# electromiografo.net
KiCad netlist of a schematic drawn in EAGLE
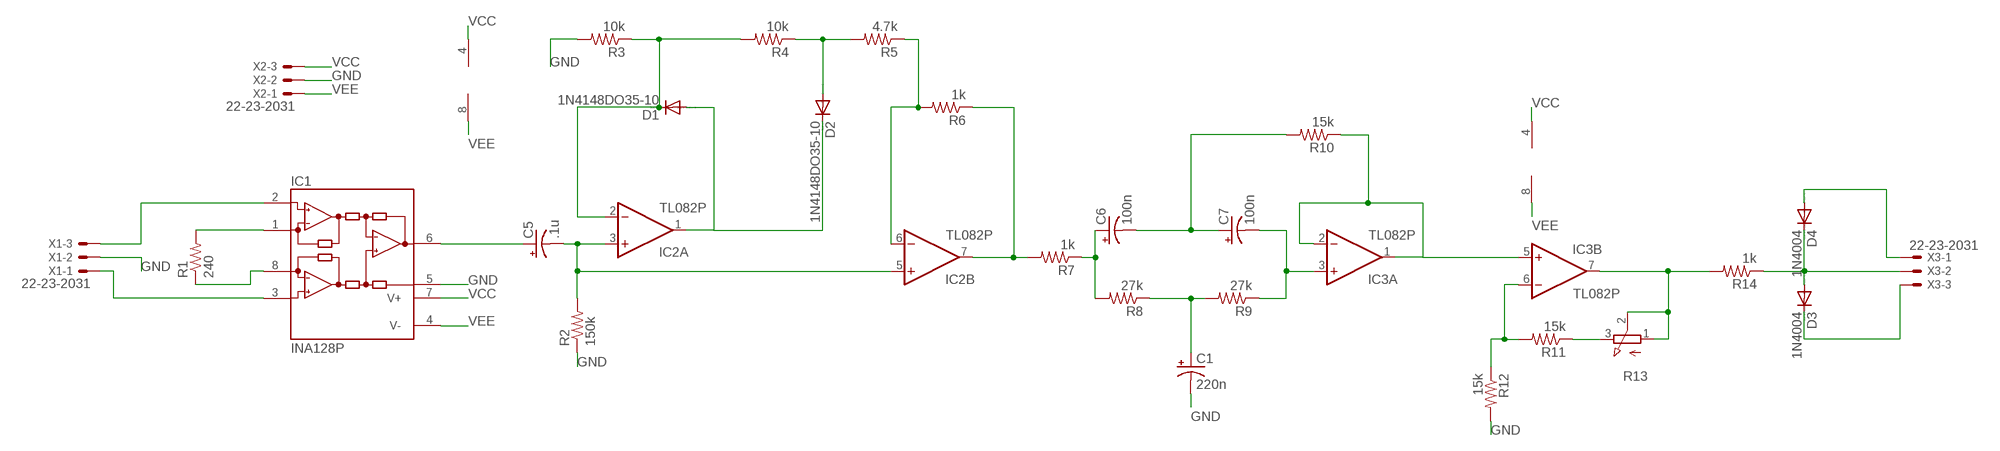
[diagram p0: schematic, sheet 1]

(export (version "E")
  (design (tool "Eeschema 10.0.6"))
  (components
    (comp (ref "C1")
      (value "220n")
      (footprint "eagle-import:E2-5")
      (libsource (lib "eagle-import") (part "CPOL-USE2-5"))
    )
    (comp (ref "C5")
      (value ".1u")
      (footprint "eagle-import:E2-5")
      (libsource (lib "eagle-import") (part "CPOL-USE2-5"))
    )
    (comp (ref "C6")
      (value "100n")
      (footprint "eagle-import:E2-5")
      (libsource (lib "eagle-import") (part "CPOL-USE2-5"))
    )
    (comp (ref "C7")
      (value "100n")
      (footprint "eagle-import:E2-5")
      (libsource (lib "eagle-import") (part "CPOL-USE2-5"))
    )
    (comp (ref "D1")
      (value "1N4148DO35-10")
      (footprint "eagle-import:DO35-10")
      (libsource (lib "eagle-import") (part "1N4148DO35-10"))
    )
    (comp (ref "D2")
      (value "1N4148DO35-10")
      (footprint "eagle-import:DO35-10")
      (libsource (lib "eagle-import") (part "1N4148DO35-10"))
    )
    (comp (ref "D3")
      (value "1N4004")
      (footprint "eagle-import:DO41-10")
      (libsource (lib "eagle-import") (part "1N4004"))
    )
    (comp (ref "D4")
      (value "1N4004")
      (footprint "eagle-import:DO41-10")
      (libsource (lib "eagle-import") (part "1N4004"))
    )
    (comp (ref "IC1")
      (value "INA128P")
      (footprint "eagle-import:DIL08")
      (fields (field (name "MF") "TEXAS INSTRUMENTS"))
      (libsource (lib "eagle-import") (part "INA128P"))
    )
    (comp (ref "IC2")
      (value "TL082P")
      (footprint "eagle-import:DIL08")
      (libsource (lib "eagle-import") (part "TL082P"))
    )
    (comp (ref "IC3")
      (value "TL082P")
      (footprint "eagle-import:DIL08")
      (libsource (lib "eagle-import") (part "TL082P"))
    )
    (comp (ref "R1")
      (value "240")
      (footprint "eagle-import:0207_12")
      (libsource (lib "eagle-import") (part "R-US_0207/12"))
    )
    (comp (ref "R2")
      (value "150k")
      (footprint "eagle-import:0207_12")
      (libsource (lib "eagle-import") (part "R-US_0207/12"))
    )
    (comp (ref "R3")
      (value "10k")
      (footprint "eagle-import:0207_12")
      (libsource (lib "eagle-import") (part "R-US_0207/12"))
    )
    (comp (ref "R4")
      (value "10k")
      (footprint "eagle-import:0207_12")
      (libsource (lib "eagle-import") (part "R-US_0207/12"))
    )
    (comp (ref "R5")
      (value "4.7k")
      (footprint "eagle-import:0207_12")
      (libsource (lib "eagle-import") (part "R-US_0207/12"))
    )
    (comp (ref "R6")
      (value "1k")
      (footprint "eagle-import:0207_12")
      (libsource (lib "eagle-import") (part "R-US_0207/12"))
    )
    (comp (ref "R7")
      (value "1k")
      (footprint "eagle-import:0207_12")
      (libsource (lib "eagle-import") (part "R-US_0207/12"))
    )
    (comp (ref "R8")
      (value "27k")
      (footprint "eagle-import:0207_12")
      (libsource (lib "eagle-import") (part "R-US_0207/12"))
    )
    (comp (ref "R9")
      (value "27k")
      (footprint "eagle-import:0207_12")
      (libsource (lib "eagle-import") (part "R-US_0207/12"))
    )
    (comp (ref "R10")
      (value "15k")
      (footprint "eagle-import:0207_12")
      (libsource (lib "eagle-import") (part "R-US_0207/12"))
    )
    (comp (ref "R11")
      (value "15k")
      (footprint "eagle-import:0207_12")
      (libsource (lib "eagle-import") (part "R-US_0207/12"))
    )
    (comp (ref "R12")
      (value "15k")
      (footprint "eagle-import:0207_12")
      (libsource (lib "eagle-import") (part "R-US_0207/12"))
    )
    (comp (ref "R13")
      (value "3RP/1610N")
      (footprint "eagle-import:3RP_1610N")
      (libsource (lib "eagle-import") (part "3RP/1610N"))
    )
    (comp (ref "R14")
      (value "1k")
      (footprint "eagle-import:0207_12")
      (libsource (lib "eagle-import") (part "R-US_0207/12"))
    )
    (comp (ref "X1")
      (value "22-23-2031")
      (footprint "eagle-import:22-23-2031")
      (fields (field (name "MF") "MOLEX"))
      (libsource (lib "eagle-import") (part "22-23-2031"))
    )
    (comp (ref "X2")
      (value "22-23-2031")
      (footprint "eagle-import:22-23-2031")
      (fields (field (name "MF") "MOLEX"))
      (libsource (lib "eagle-import") (part "22-23-2031"))
    )
    (comp (ref "X3")
      (value "22-23-2031")
      (footprint "eagle-import:22-23-2031")
      (fields (field (name "MF") "MOLEX"))
      (libsource (lib "eagle-import") (part "22-23-2031"))
    )
  )
  (nets
    (net (code "1") (name "/GND") (class "Default")
      (node (ref "C1") (pin "-") (pinfunction "-_-") (pintype "passive"))
      (node (ref "IC1") (pin "5") (pinfunction "REF_5") (pintype "passive"))
      (node (ref "R12") (pin "2") (pinfunction "2_2") (pintype "passive"))
      (node (ref "R2") (pin "1") (pinfunction "1_1") (pintype "passive"))
      (node (ref "R3") (pin "2") (pinfunction "2_2") (pintype "passive"))
      (node (ref "X1") (pin "2") (pinfunction "S_2") (pintype "passive"))
      (node (ref "X2") (pin "2") (pinfunction "S_2") (pintype "passive"))
    )
    (net (code "2") (name "/VCC") (class "Default")
      (node (ref "IC1") (pin "7") (pinfunction "V+_7") (pintype "power_in"))
      (node (ref "IC2") (pin "4") (pinfunction "V-_4") (pintype "power_in"))
      (node (ref "IC3") (pin "4") (pinfunction "V-_4") (pintype "power_in"))
      (node (ref "X2") (pin "3") (pinfunction "S_3") (pintype "passive"))
    )
    (net (code "3") (name "/VEE") (class "Default")
      (node (ref "IC1") (pin "4") (pinfunction "V-_4") (pintype "power_in"))
      (node (ref "IC2") (pin "8") (pinfunction "V+_8") (pintype "power_in"))
      (node (ref "IC3") (pin "8") (pinfunction "V+_8") (pintype "power_in"))
      (node (ref "X2") (pin "1") (pinfunction "S_1") (pintype "passive"))
    )
    (net (code "4") (name "Net-(C1-Pad+)") (class "Default")
      (node (ref "C1") (pin "+") (pinfunction "+_+") (pintype "passive"))
      (node (ref "R8") (pin "1") (pinfunction "1_1") (pintype "passive"))
      (node (ref "R9") (pin "2") (pinfunction "2_2") (pintype "passive"))
    )
    (net (code "5") (name "Net-(C6-Pad+)") (class "Default")
      (node (ref "C6") (pin "+") (pinfunction "+_+") (pintype "passive"))
      (node (ref "R7") (pin "1") (pinfunction "1_1") (pintype "passive"))
      (node (ref "R8") (pin "2") (pinfunction "2_2") (pintype "passive"))
    )
    (net (code "6") (name "Net-(C6-Pad-)") (class "Default")
      (node (ref "C6") (pin "-") (pinfunction "-_-") (pintype "passive"))
      (node (ref "C7") (pin "+") (pinfunction "+_+") (pintype "passive"))
      (node (ref "R10") (pin "2") (pinfunction "2_2") (pintype "passive"))
    )
    (net (code "7") (name "Net-(D2-PadA)") (class "Default")
      (node (ref "D2") (pin "A") (pinfunction "A_A") (pintype "passive"))
      (node (ref "R4") (pin "1") (pinfunction "1_1") (pintype "passive"))
      (node (ref "R5") (pin "2") (pinfunction "2_2") (pintype "passive"))
    )
    (net (code "8") (name "Net-(IC1-+IN)") (class "Default")
      (node (ref "IC1") (pin "3") (pinfunction "+IN_3") (pintype "input"))
      (node (ref "X1") (pin "1") (pinfunction "S_1") (pintype "passive"))
    )
    (net (code "9") (name "Net-(IC1--IN)") (class "Default")
      (node (ref "IC1") (pin "2") (pinfunction "-IN_2") (pintype "input"))
      (node (ref "X1") (pin "3") (pinfunction "S_3") (pintype "passive"))
    )
    (net (code "10") (name "Net-(IC1-OUT)") (class "Default")
      (node (ref "C5") (pin "+") (pinfunction "+_+") (pintype "passive"))
      (node (ref "IC1") (pin "6") (pinfunction "OUT_6") (pintype "output"))
    )
    (net (code "11") (name "Net-(IC1-RG-Pad1)") (class "Default")
      (node (ref "IC1") (pin "1") (pinfunction "RG_1") (pintype "passive"))
      (node (ref "R1") (pin "2") (pinfunction "2_2") (pintype "passive"))
    )
    (net (code "12") (name "Net-(IC1-RG-Pad8)") (class "Default")
      (node (ref "IC1") (pin "8") (pinfunction "RG_8") (pintype "passive"))
      (node (ref "R1") (pin "1") (pinfunction "1_1") (pintype "passive"))
    )
    (net (code "13") (name "Net-(IC2A-+IN)") (class "Default")
      (node (ref "C5") (pin "-") (pinfunction "-_-") (pintype "passive"))
      (node (ref "IC2") (pin "3") (pinfunction "+IN_3") (pintype "input"))
      (node (ref "IC2") (pin "5") (pinfunction "+IN_5") (pintype "input"))
      (node (ref "R2") (pin "2") (pinfunction "2_2") (pintype "passive"))
    )
    (net (code "14") (name "Net-(IC2A--IN)") (class "Default")
      (node (ref "D1") (pin "C") (pinfunction "C_C") (pintype "passive"))
      (node (ref "IC2") (pin "2") (pinfunction "-IN_2") (pintype "input"))
      (node (ref "R3") (pin "1") (pinfunction "1_1") (pintype "passive"))
      (node (ref "R4") (pin "2") (pinfunction "2_2") (pintype "passive"))
    )
    (net (code "15") (name "Net-(IC2A-OUT)") (class "Default")
      (node (ref "D1") (pin "A") (pinfunction "A_A") (pintype "passive"))
      (node (ref "D2") (pin "C") (pinfunction "C_C") (pintype "passive"))
      (node (ref "IC2") (pin "1") (pinfunction "OUT_1") (pintype "output"))
    )
    (net (code "16") (name "Net-(IC2B--IN)") (class "Default")
      (node (ref "IC2") (pin "6") (pinfunction "-IN_6") (pintype "input"))
      (node (ref "R5") (pin "1") (pinfunction "1_1") (pintype "passive"))
      (node (ref "R6") (pin "2") (pinfunction "2_2") (pintype "passive"))
    )
    (net (code "17") (name "Net-(IC2B-OUT)") (class "Default")
      (node (ref "IC2") (pin "7") (pinfunction "OUT_7") (pintype "output"))
      (node (ref "R6") (pin "1") (pinfunction "1_1") (pintype "passive"))
      (node (ref "R7") (pin "2") (pinfunction "2_2") (pintype "passive"))
    )
    (net (code "18") (name "Net-(IC3A-+IN)") (class "Default")
      (node (ref "C7") (pin "-") (pinfunction "-_-") (pintype "passive"))
      (node (ref "IC3") (pin "3") (pinfunction "+IN_3") (pintype "input"))
      (node (ref "R9") (pin "1") (pinfunction "1_1") (pintype "passive"))
    )
    (net (code "19") (name "Net-(IC3A--IN)") (class "Default")
      (node (ref "IC3") (pin "1") (pinfunction "OUT_1") (pintype "output"))
      (node (ref "IC3") (pin "2") (pinfunction "-IN_2") (pintype "input"))
      (node (ref "IC3") (pin "5") (pinfunction "+IN_5") (pintype "input"))
      (node (ref "R10") (pin "1") (pinfunction "1_1") (pintype "passive"))
    )
    (net (code "20") (name "Net-(IC3B--IN)") (class "Default")
      (node (ref "IC3") (pin "6") (pinfunction "-IN_6") (pintype "input"))
      (node (ref "R11") (pin "2") (pinfunction "2_2") (pintype "passive"))
      (node (ref "R12") (pin "1") (pinfunction "1_1") (pintype "passive"))
    )
    (net (code "21") (name "Net-(IC3B-OUT)") (class "Default")
      (node (ref "IC3") (pin "7") (pinfunction "OUT_7") (pintype "output"))
      (node (ref "R13") (pin "1") (pinfunction "A_1") (pintype "passive"))
      (node (ref "R13") (pin "2") (pinfunction "S_2") (pintype "passive"))
      (node (ref "R14") (pin "2") (pinfunction "2_2") (pintype "passive"))
    )
    (net (code "22") (name "Net-(R13-E)") (class "Default")
      (node (ref "R11") (pin "1") (pinfunction "1_1") (pintype "passive"))
      (node (ref "R13") (pin "3") (pinfunction "E_3") (pintype "passive"))
    )
    (net (code "23") (name "Net-(X3A-S)") (class "Default")
      (node (ref "D4") (pin "A") (pinfunction "A_A") (pintype "passive"))
      (node (ref "X3") (pin "1") (pinfunction "S_1") (pintype "passive"))
    )
    (net (code "24") (name "Net-(X3B-S)") (class "Default")
      (node (ref "D3") (pin "A") (pinfunction "A_A") (pintype "passive"))
      (node (ref "D4") (pin "C") (pinfunction "C_C") (pintype "passive"))
      (node (ref "R14") (pin "1") (pinfunction "1_1") (pintype "passive"))
      (node (ref "X3") (pin "2") (pinfunction "S_2") (pintype "passive"))
    )
    (net (code "25") (name "Net-(X3C-S)") (class "Default")
      (node (ref "D3") (pin "C") (pinfunction "C_C") (pintype "passive"))
      (node (ref "X3") (pin "3") (pinfunction "S_3") (pintype "passive"))
    )
  )
)
